# IR_Sensor_Block.net
KiCad netlist of a schematic drawn in Altium Designer
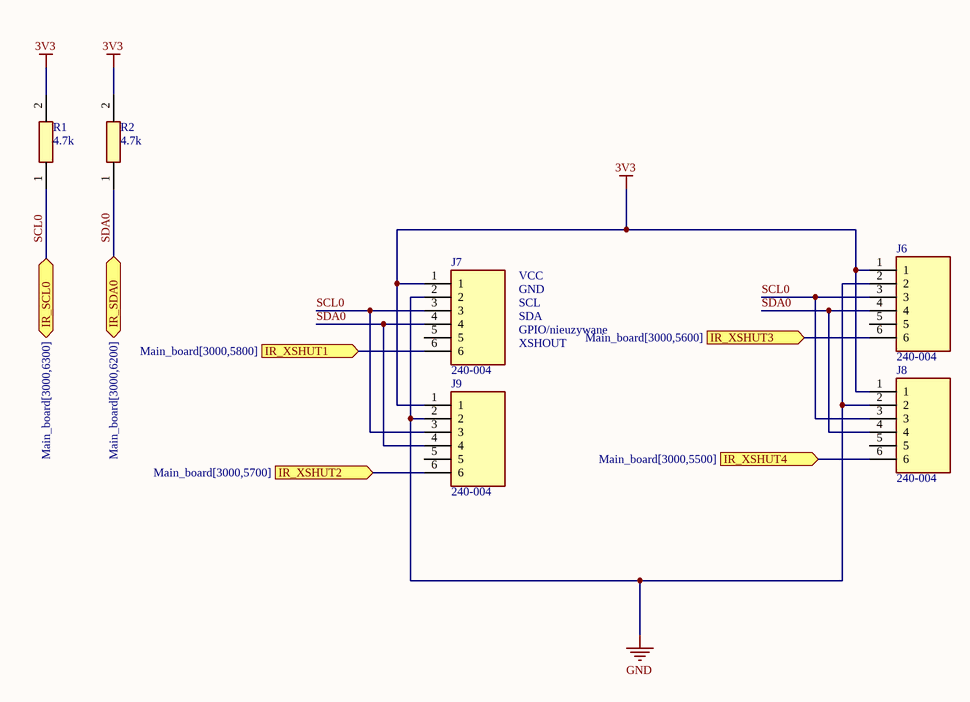
[diagram p0: IR_Sensor_Block.SchDoc]

(export (version "E")
  (design (tool "Eeschema 10.0.6"))
  (components
    (comp (ref "J6")
      (value "240-004")
      (footprint "SamacSys:HDRV6W64P0X254_1X6_1524X254X909P")
      (description "Connector")
      (libsource (lib "SamacSys") (part "240-004"))
    )
    (comp (ref "J7")
      (value "240-004")
      (footprint "SamacSys:HDRV6W64P0X254_1X6_1524X254X909P")
      (description "Connector")
      (libsource (lib "SamacSys") (part "240-004"))
    )
    (comp (ref "J8")
      (value "240-004")
      (footprint "SamacSys:HDRV6W64P0X254_1X6_1524X254X909P")
      (description "Connector")
      (libsource (lib "SamacSys") (part "240-004"))
    )
    (comp (ref "J9")
      (value "240-004")
      (footprint "SamacSys:HDRV6W64P0X254_1X6_1524X254X909P")
      (description "Connector")
      (libsource (lib "SamacSys") (part "240-004"))
    )
    (comp (ref "R1")
      (value "4.7k")
      (footprint "SamacSys:RESC1608X55N")
      (description "Resistor")
      (fields
        (field (name "MANUFACTURER_PART_NUMBER") "RMCF0603FT4K70")
        (field (name "MOUSER PART NUMBER") "708-RMCF0603FT4K70")
      )
      (libsource (lib "*") (part "RMCF0603FT4K70"))
    )
    (comp (ref "R2")
      (value "4.7k")
      (footprint "SamacSys:RESC1608X55N")
      (description "Resistor")
      (fields
        (field (name "MANUFACTURER_PART_NUMBER") "RMCF0603FT4K70")
        (field (name "MOUSER PART NUMBER") "708-RMCF0603FT4K70")
      )
      (libsource (lib "*") (part "RMCF0603FT4K70"))
    )
  )
  (nets
    (net (code "1") (name "/IR_XSHUT1") (class "Default")
      (node (ref "J7") (pin "6") (pinfunction "6_6") (pintype "passive"))
    )
    (net (code "2") (name "/IR_XSHUT2") (class "Default")
      (node (ref "J9") (pin "6") (pinfunction "6_6") (pintype "passive"))
    )
    (net (code "3") (name "/IR_XSHUT3") (class "Default")
      (node (ref "J6") (pin "6") (pinfunction "6_6") (pintype "passive"))
    )
    (net (code "4") (name "/IR_XSHUT4") (class "Default")
      (node (ref "J8") (pin "6") (pinfunction "6_6") (pintype "passive"))
    )
    (net (code "5") (name "/SCL0") (class "Default")
      (node (ref "J6") (pin "3") (pinfunction "3_3") (pintype "passive"))
      (node (ref "J7") (pin "3") (pinfunction "3_3") (pintype "passive"))
      (node (ref "J8") (pin "3") (pinfunction "3_3") (pintype "passive"))
      (node (ref "J9") (pin "3") (pinfunction "3_3") (pintype "passive"))
      (node (ref "R1") (pin "1") (pinfunction "1_1") (pintype "passive"))
    )
    (net (code "6") (name "/SDA0") (class "Default")
      (node (ref "J6") (pin "4") (pinfunction "4_4") (pintype "passive"))
      (node (ref "J7") (pin "4") (pinfunction "4_4") (pintype "passive"))
      (node (ref "J8") (pin "4") (pinfunction "4_4") (pintype "passive"))
      (node (ref "J9") (pin "4") (pinfunction "4_4") (pintype "passive"))
      (node (ref "R2") (pin "1") (pinfunction "1_1") (pintype "passive"))
    )
    (net (code "7") (name "3V3") (class "Default")
      (node (ref "J6") (pin "1") (pinfunction "1_1") (pintype "passive"))
      (node (ref "J7") (pin "1") (pinfunction "1_1") (pintype "passive"))
      (node (ref "J8") (pin "1") (pinfunction "1_1") (pintype "passive"))
      (node (ref "J9") (pin "1") (pinfunction "1_1") (pintype "passive"))
      (node (ref "R1") (pin "2") (pinfunction "2_2") (pintype "passive"))
      (node (ref "R2") (pin "2") (pinfunction "2_2") (pintype "passive"))
    )
    (net (code "8") (name "GND") (class "Default")
      (node (ref "J6") (pin "2") (pinfunction "2_2") (pintype "passive"))
      (node (ref "J7") (pin "2") (pinfunction "2_2") (pintype "passive"))
      (node (ref "J8") (pin "2") (pinfunction "2_2") (pintype "passive"))
      (node (ref "J9") (pin "2") (pinfunction "2_2") (pintype "passive"))
    )
    (net (code "9") (name "unconnected-(J6-Pad5)") (class "Default")
      (node (ref "J6") (pin "5") (pinfunction "5_5") (pintype "passive"))
    )
    (net (code "10") (name "unconnected-(J7-Pad5)") (class "Default")
      (node (ref "J7") (pin "5") (pinfunction "5_5") (pintype "passive"))
    )
    (net (code "11") (name "unconnected-(J8-Pad5)") (class "Default")
      (node (ref "J8") (pin "5") (pinfunction "5_5") (pintype "passive"))
    )
    (net (code "12") (name "unconnected-(J9-Pad5)") (class "Default")
      (node (ref "J9") (pin "5") (pinfunction "5_5") (pintype "passive"))
    )
  )
)
